# STorM32_NT_imu_v11-mpu9250.net
KiCad netlist of a schematic drawn in EAGLE
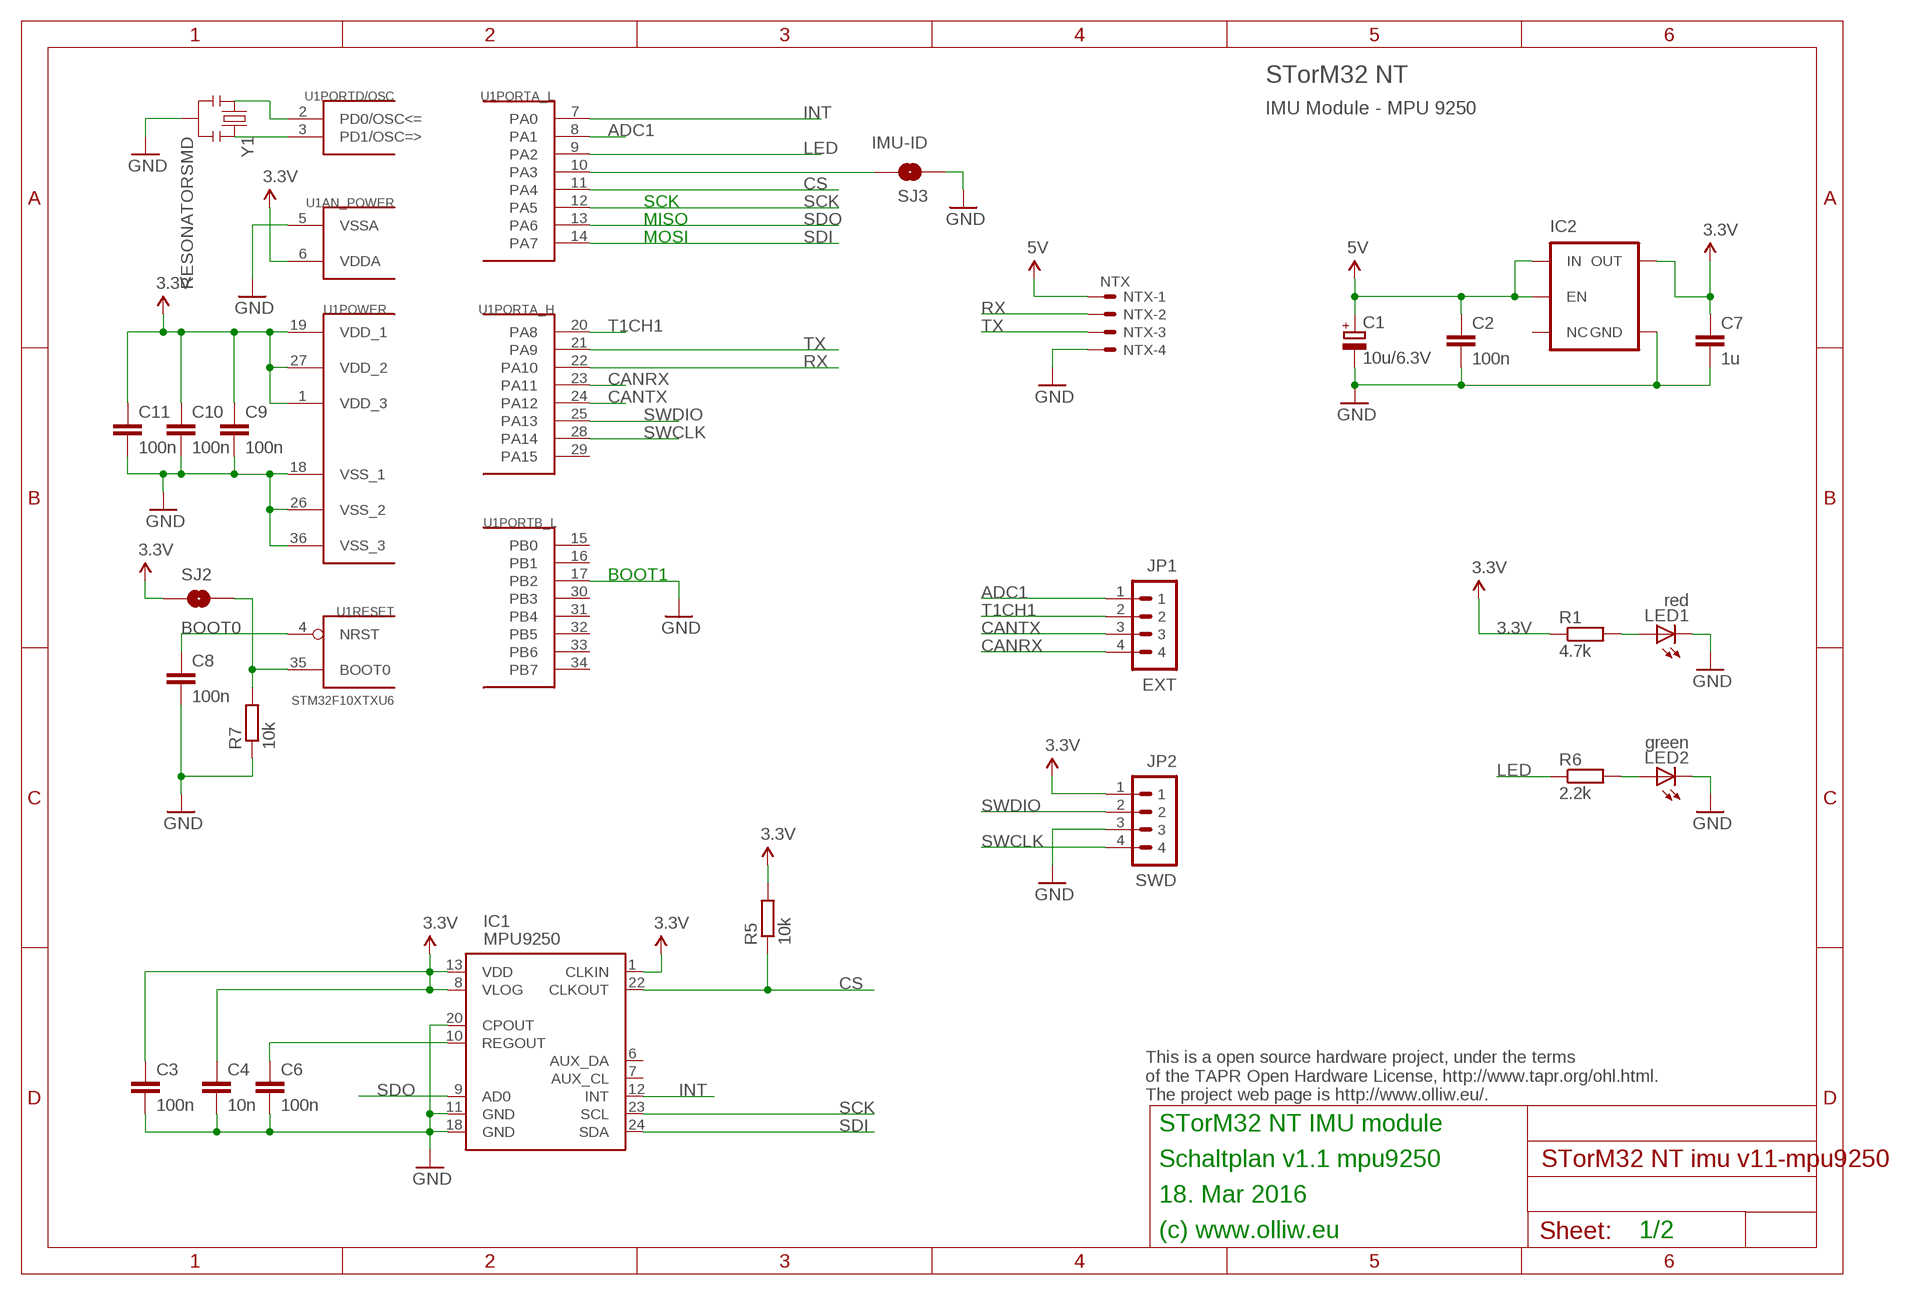
[diagram p0: schematic, sheet 1]

(export (version "E")
  (design (tool "Eeschema 10.0.6"))
  (components
    (comp (ref "C1")
      (value "10u/6.3V")
      (footprint "eagle-import:SMC_B")
      (libsource (lib "eagle-import") (part "CPOL-EUSMCB"))
    )
    (comp (ref "C2")
      (value "100n")
      (footprint "eagle-import:C0603")
      (libsource (lib "eagle-import") (part "C-EUC0603"))
    )
    (comp (ref "C3")
      (value "100n")
      (footprint "eagle-import:C0603")
      (libsource (lib "eagle-import") (part "C-EUC0603"))
    )
    (comp (ref "C4")
      (value "10n")
      (footprint "eagle-import:C0603")
      (libsource (lib "eagle-import") (part "C-EUC0603"))
    )
    (comp (ref "C6")
      (value "100n")
      (footprint "eagle-import:C0603")
      (libsource (lib "eagle-import") (part "C-EUC0603"))
    )
    (comp (ref "C7")
      (value "1u")
      (footprint "eagle-import:C0603")
      (libsource (lib "eagle-import") (part "C-EUC0603"))
    )
    (comp (ref "C8")
      (value "100n")
      (footprint "eagle-import:C0603")
      (libsource (lib "eagle-import") (part "C-EUC0603"))
    )
    (comp (ref "C9")
      (value "100n")
      (footprint "eagle-import:C0603")
      (libsource (lib "eagle-import") (part "C-EUC0603"))
    )
    (comp (ref "C10")
      (value "100n")
      (footprint "eagle-import:C0603")
      (libsource (lib "eagle-import") (part "C-EUC0603"))
    )
    (comp (ref "C11")
      (value "100n")
      (footprint "eagle-import:C0603")
      (libsource (lib "eagle-import") (part "C-EUC0603"))
    )
    (comp (ref "IC1")
      (value "MPU9250")
      (footprint "eagle-import:QFN-24-3X3")
      (libsource (lib "eagle-import") (part "IMU3000QFN-24-0.4MIL"))
    )
    (comp (ref "IC2")
      (value "V_REG_TPS76433SOT23-5")
      (footprint "eagle-import:SOT23-5")
      (libsource (lib "eagle-import") (part "V_REG_TPS76433SOT23-5"))
    )
    (comp (ref "JP1")
      (value "EXT")
      (footprint "eagle-import:4X1_1P27_OCT_BILEX")
      (libsource (lib "eagle-import") (part "P4X1_1P27-OCT_BILEX"))
    )
    (comp (ref "JP2")
      (value "SWD")
      (footprint "eagle-import:4X1_1P27_OCT_BILEX")
      (libsource (lib "eagle-import") (part "P4X1_1P27-OCT_BILEX"))
    )
    (comp (ref "LED1")
      (value "red")
      (footprint "eagle-import:CHIPLED_0603")
      (libsource (lib "eagle-import") (part "LEDCHIPLED_0603"))
    )
    (comp (ref "LED2")
      (value "green")
      (footprint "eagle-import:CHIPLED_0603")
      (libsource (lib "eagle-import") (part "LEDCHIPLED_0603"))
    )
    (comp (ref "NTX")
      (value "NTX")
      (footprint "eagle-import:SM04B-SRSS-TB")
      (libsource (lib "eagle-import") (part "?M04B-SRSS-TBS"))
    )
    (comp (ref "R1")
      (value "4.7k")
      (footprint "eagle-import:R0603")
      (libsource (lib "eagle-import") (part "R-EU_R0603"))
    )
    (comp (ref "R5")
      (value "10k")
      (footprint "eagle-import:R0603")
      (libsource (lib "eagle-import") (part "R-EU_R0603"))
    )
    (comp (ref "R6")
      (value "2.2k")
      (footprint "eagle-import:R0603")
      (libsource (lib "eagle-import") (part "R-EU_R0603"))
    )
    (comp (ref "R7")
      (value "10k")
      (footprint "eagle-import:R0603")
      (libsource (lib "eagle-import") (part "R-EU_R0603"))
    )
    (comp (ref "SJ2")
      (value "BOOT0")
      (footprint "eagle-import:SJ_2S-NO")
      (libsource (lib "eagle-import") (part "SOLDERJUMPERNO"))
    )
    (comp (ref "SJ3")
      (value "IMU-ID")
      (footprint "eagle-import:SJ_2S-NO")
      (libsource (lib "eagle-import") (part "SOLDERJUMPERNO"))
    )
    (comp (ref "U1")
      (value "STM32F10XTXU6")
      (footprint "eagle-import:VFQFPN36")
      (libsource (lib "eagle-import") (part "STM32F10XTXU6"))
    )
    (comp (ref "Y1")
      (value "RESONATORSMD")
      (footprint "eagle-import:RESONATOR-SMD")
      (libsource (lib "eagle-import") (part "RESONATORSMD"))
    )
  )
  (nets
    (net (code "1") (name "/ADC1") (class "Default")
      (node (ref "JP1") (pin "1") (pinfunction "1_1") (pintype "passive"))
      (node (ref "U1") (pin "8") (pinfunction "PA1_8") (pintype "bidirectional"))
    )
    (net (code "2") (name "/CANRX") (class "Default")
      (node (ref "JP1") (pin "4") (pinfunction "4_4") (pintype "passive"))
      (node (ref "U1") (pin "23") (pinfunction "PA11_23") (pintype "bidirectional"))
    )
    (net (code "3") (name "/CANTX") (class "Default")
      (node (ref "JP1") (pin "3") (pinfunction "3_3") (pintype "passive"))
      (node (ref "U1") (pin "24") (pinfunction "PA12_24") (pintype "bidirectional"))
    )
    (net (code "4") (name "/CS") (class "Default")
      (node (ref "IC1") (pin "22") (pinfunction "CLKOUT_22") (pintype "bidirectional"))
      (node (ref "R5") (pin "1") (pinfunction "1_1") (pintype "passive"))
      (node (ref "U1") (pin "11") (pinfunction "PA4_11") (pintype "bidirectional"))
    )
    (net (code "5") (name "/INT") (class "Default")
      (node (ref "IC1") (pin "12") (pinfunction "INT_12") (pintype "bidirectional"))
      (node (ref "U1") (pin "7") (pinfunction "PA0_7") (pintype "bidirectional"))
    )
    (net (code "6") (name "/LED") (class "Default")
      (node (ref "R6") (pin "1") (pinfunction "1_1") (pintype "passive"))
      (node (ref "U1") (pin "9") (pinfunction "PA2_9") (pintype "bidirectional"))
    )
    (net (code "7") (name "/RX") (class "Default")
      (node (ref "NTX") (pin "2") (pinfunction "S_2") (pintype "passive"))
      (node (ref "U1") (pin "22") (pinfunction "PA10_22") (pintype "bidirectional"))
    )
    (net (code "8") (name "/SCK") (class "Default")
      (node (ref "IC1") (pin "23") (pinfunction "SCL_23") (pintype "bidirectional"))
      (node (ref "U1") (pin "12") (pinfunction "PA5_12") (pintype "bidirectional"))
    )
    (net (code "9") (name "/SDI") (class "Default")
      (node (ref "IC1") (pin "24") (pinfunction "SDA_24") (pintype "bidirectional"))
      (node (ref "U1") (pin "14") (pinfunction "PA7_14") (pintype "bidirectional"))
    )
    (net (code "10") (name "/SDO") (class "Default")
      (node (ref "IC1") (pin "9") (pinfunction "AD0_9") (pintype "bidirectional"))
      (node (ref "U1") (pin "13") (pinfunction "PA6_13") (pintype "bidirectional"))
    )
    (net (code "11") (name "/SWCLK") (class "Default")
      (node (ref "JP2") (pin "4") (pinfunction "4_4") (pintype "passive"))
      (node (ref "U1") (pin "28") (pinfunction "PA14_28") (pintype "bidirectional"))
    )
    (net (code "12") (name "/SWDIO") (class "Default")
      (node (ref "JP2") (pin "2") (pinfunction "2_2") (pintype "passive"))
      (node (ref "U1") (pin "25") (pinfunction "PA13_25") (pintype "bidirectional"))
    )
    (net (code "13") (name "/T1CH1") (class "Default")
      (node (ref "JP1") (pin "2") (pinfunction "2_2") (pintype "passive"))
      (node (ref "U1") (pin "20") (pinfunction "PA8_20") (pintype "bidirectional"))
    )
    (net (code "14") (name "/TX") (class "Default")
      (node (ref "NTX") (pin "3") (pinfunction "S_3") (pintype "passive"))
      (node (ref "U1") (pin "21") (pinfunction "PA9_21") (pintype "bidirectional"))
    )
    (net (code "15") (name "3.3V") (class "Default")
      (node (ref "C10") (pin "1") (pinfunction "1_1") (pintype "passive"))
      (node (ref "C11") (pin "1") (pinfunction "1_1") (pintype "passive"))
      (node (ref "C3") (pin "1") (pinfunction "1_1") (pintype "passive"))
      (node (ref "C4") (pin "1") (pinfunction "1_1") (pintype "passive"))
      (node (ref "C7") (pin "1") (pinfunction "1_1") (pintype "passive"))
      (node (ref "C9") (pin "1") (pinfunction "1_1") (pintype "passive"))
      (node (ref "IC1") (pin "1") (pinfunction "CLKIN_1") (pintype "bidirectional"))
      (node (ref "IC1") (pin "13") (pinfunction "VDD_13") (pintype "bidirectional"))
      (node (ref "IC1") (pin "8") (pinfunction "VLOG_8") (pintype "bidirectional"))
      (node (ref "IC2") (pin "5") (pinfunction "OUT_5") (pintype "passive"))
      (node (ref "JP2") (pin "1") (pinfunction "1_1") (pintype "passive"))
      (node (ref "R1") (pin "1") (pinfunction "1_1") (pintype "passive"))
      (node (ref "R5") (pin "2") (pinfunction "2_2") (pintype "passive"))
      (node (ref "SJ2") (pin "1") (pinfunction "1_1") (pintype "passive"))
      (node (ref "U1") (pin "1") (pinfunction "VDD_3_1") (pintype "power_in"))
      (node (ref "U1") (pin "19") (pinfunction "VDD_1_19") (pintype "power_in"))
      (node (ref "U1") (pin "27") (pinfunction "VDD_2_27") (pintype "power_in"))
      (node (ref "U1") (pin "6") (pinfunction "VDDA_6") (pintype "power_in"))
    )
    (net (code "16") (name "5V") (class "Default")
      (node (ref "C1") (pin "+") (pinfunction "+_+") (pintype "passive"))
      (node (ref "C2") (pin "1") (pinfunction "1_1") (pintype "passive"))
      (node (ref "IC2") (pin "1") (pinfunction "IN_1") (pintype "input"))
      (node (ref "IC2") (pin "3") (pinfunction "EN_3") (pintype "input"))
      (node (ref "NTX") (pin "1") (pinfunction "S_1") (pintype "passive"))
    )
    (net (code "17") (name "GND") (class "Default")
      (node (ref "C1") (pin "-") (pinfunction "-_-") (pintype "passive"))
      (node (ref "C10") (pin "2") (pinfunction "2_2") (pintype "passive"))
      (node (ref "C11") (pin "2") (pinfunction "2_2") (pintype "passive"))
      (node (ref "C2") (pin "2") (pinfunction "2_2") (pintype "passive"))
      (node (ref "C3") (pin "2") (pinfunction "2_2") (pintype "passive"))
      (node (ref "C4") (pin "2") (pinfunction "2_2") (pintype "passive"))
      (node (ref "C6") (pin "2") (pinfunction "2_2") (pintype "passive"))
      (node (ref "C7") (pin "2") (pinfunction "2_2") (pintype "passive"))
      (node (ref "C8") (pin "2") (pinfunction "2_2") (pintype "passive"))
      (node (ref "C9") (pin "2") (pinfunction "2_2") (pintype "passive"))
      (node (ref "IC1") (pin "11") (pinfunction "GND_11") (pintype "bidirectional"))
      (node (ref "IC1") (pin "18") (pinfunction "GND_18") (pintype "bidirectional"))
      (node (ref "IC1") (pin "20") (pinfunction "CPOUT_20") (pintype "bidirectional"))
      (node (ref "IC2") (pin "2") (pinfunction "GND_2") (pintype "input"))
      (node (ref "JP2") (pin "3") (pinfunction "3_3") (pintype "passive"))
      (node (ref "LED1") (pin "C") (pinfunction "C_C") (pintype "passive"))
      (node (ref "LED2") (pin "C") (pinfunction "C_C") (pintype "passive"))
      (node (ref "NTX") (pin "4") (pinfunction "S_4") (pintype "passive"))
      (node (ref "R7") (pin "1") (pinfunction "1_1") (pintype "passive"))
      (node (ref "SJ3") (pin "1") (pinfunction "1_1") (pintype "passive"))
      (node (ref "U1") (pin "17") (pinfunction "PB2_17") (pintype "bidirectional"))
      (node (ref "U1") (pin "18") (pinfunction "VSS_1_18") (pintype "power_in"))
      (node (ref "U1") (pin "26") (pinfunction "VSS_2_26") (pintype "power_in"))
      (node (ref "U1") (pin "36") (pinfunction "VSS_3_36") (pintype "power_in"))
      (node (ref "U1") (pin "5") (pinfunction "VSSA_5") (pintype "power_in"))
      (node (ref "Y1") (pin "2") (pinfunction "2_2") (pintype "passive"))
    )
    (net (code "18") (name "Net-(IC1-REGOUT)") (class "Default")
      (node (ref "C6") (pin "1") (pinfunction "1_1") (pintype "passive"))
      (node (ref "IC1") (pin "10") (pinfunction "REGOUT_10") (pintype "bidirectional"))
    )
    (net (code "19") (name "Net-(LED1-PadA)") (class "Default")
      (node (ref "LED1") (pin "A") (pinfunction "A_A") (pintype "passive"))
      (node (ref "R1") (pin "2") (pinfunction "2_2") (pintype "passive"))
    )
    (net (code "20") (name "Net-(LED2-PadA)") (class "Default")
      (node (ref "LED2") (pin "A") (pinfunction "A_A") (pintype "passive"))
      (node (ref "R6") (pin "2") (pinfunction "2_2") (pintype "passive"))
    )
    (net (code "21") (name "Net-(U1C-PA3)") (class "Default")
      (node (ref "SJ3") (pin "2") (pinfunction "2_2") (pintype "passive"))
      (node (ref "U1") (pin "10") (pinfunction "PA3_10") (pintype "bidirectional"))
    )
    (net (code "22") (name "Net-(U1E-PD0{slash}OSC<=)") (class "Default")
      (node (ref "U1") (pin "2") (pinfunction "PD0/OSC<=_2") (pintype "bidirectional"))
      (node (ref "Y1") (pin "1") (pinfunction "1_1") (pintype "passive"))
    )
    (net (code "23") (name "Net-(U1E-PD1{slash}OSC=>)") (class "Default")
      (node (ref "U1") (pin "3") (pinfunction "PD1/OSC=>_3") (pintype "bidirectional"))
      (node (ref "Y1") (pin "3") (pinfunction "3_3") (pintype "passive"))
    )
    (net (code "24") (name "Net-(U1G-BOOT0)") (class "Default")
      (node (ref "R7") (pin "2") (pinfunction "2_2") (pintype "passive"))
      (node (ref "SJ2") (pin "2") (pinfunction "2_2") (pintype "passive"))
      (node (ref "U1") (pin "35") (pinfunction "BOOT0_35") (pintype "input"))
    )
    (net (code "25") (name "Net-(U1G-NRST)") (class "Default")
      (node (ref "C8") (pin "1") (pinfunction "1_1") (pintype "passive"))
      (node (ref "U1") (pin "4") (pinfunction "NRST_4") (pintype "input"))
    )
    (net (code "26") (name "unconnected-(IC1-AUX_CL-Pad7)") (class "Default")
      (node (ref "IC1") (pin "7") (pinfunction "AUX_CL_7") (pintype "bidirectional"))
    )
    (net (code "27") (name "unconnected-(IC1-AUX_DA-Pad6)") (class "Default")
      (node (ref "IC1") (pin "6") (pinfunction "AUX_DA_6") (pintype "bidirectional"))
    )
    (net (code "28") (name "unconnected-(IC2-NC-Pad4)") (class "Default")
      (node (ref "IC2") (pin "4") (pinfunction "NC_4") (pintype "input"))
    )
    (net (code "29") (name "unconnected-(U1B-PA15-Pad29)") (class "Default")
      (node (ref "U1") (pin "29") (pinfunction "PA15_29") (pintype "bidirectional"))
    )
    (net (code "30") (name "unconnected-(U1D-PB0-Pad15)") (class "Default")
      (node (ref "U1") (pin "15") (pinfunction "PB0_15") (pintype "bidirectional"))
    )
    (net (code "31") (name "unconnected-(U1D-PB1-Pad16)") (class "Default")
      (node (ref "U1") (pin "16") (pinfunction "PB1_16") (pintype "bidirectional"))
    )
    (net (code "32") (name "unconnected-(U1D-PB3-Pad30)") (class "Default")
      (node (ref "U1") (pin "30") (pinfunction "PB3_30") (pintype "bidirectional"))
    )
    (net (code "33") (name "unconnected-(U1D-PB4-Pad31)") (class "Default")
      (node (ref "U1") (pin "31") (pinfunction "PB4_31") (pintype "bidirectional"))
    )
    (net (code "34") (name "unconnected-(U1D-PB5-Pad32)") (class "Default")
      (node (ref "U1") (pin "32") (pinfunction "PB5_32") (pintype "bidirectional"))
    )
    (net (code "35") (name "unconnected-(U1D-PB6-Pad33)") (class "Default")
      (node (ref "U1") (pin "33") (pinfunction "PB6_33") (pintype "bidirectional"))
    )
    (net (code "36") (name "unconnected-(U1D-PB7-Pad34)") (class "Default")
      (node (ref "U1") (pin "34") (pinfunction "PB7_34") (pintype "bidirectional"))
    )
  )
)
